# ESP-USB.net
KiCad netlist of a schematic drawn in Altium Designer
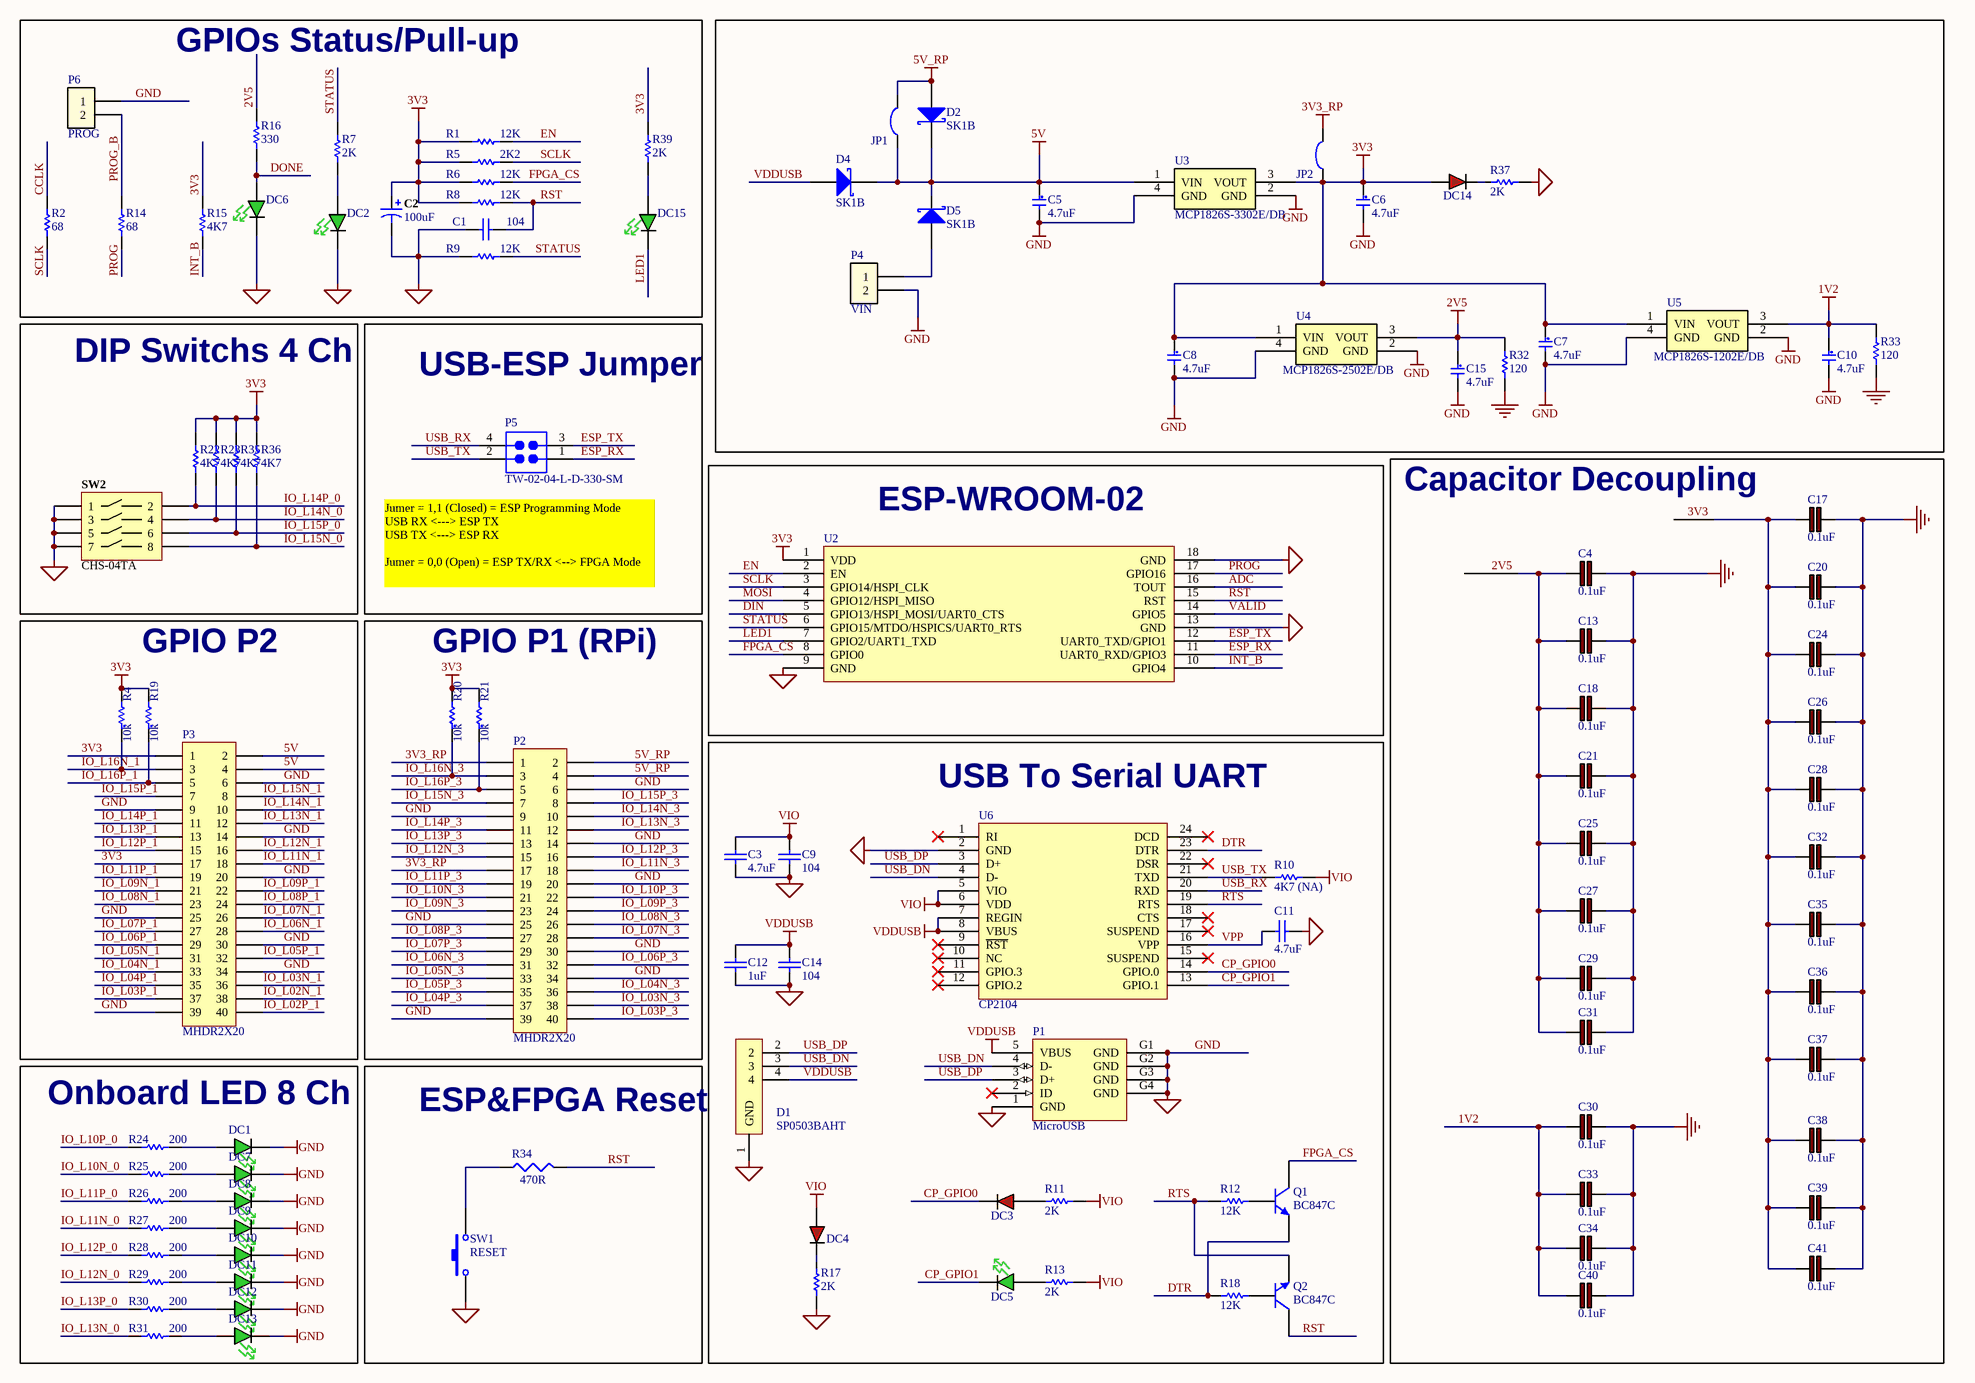
[diagram p0: ESP-USB.SchDoc]

(export (version "E")
  (design (tool "Eeschema 10.0.6"))
  (components
    (comp (ref "C1")
      (value "104")
      (footprint "C0603 - Marked")
      (description "Capacitor 0603")
      (fields (field (name "MFG") "KEMET"))
      (libsource (lib "Miscellaneous Devices") (part "Cap Semi"))
    )
    (comp (ref "C2")
      (value "100 uF Tantalum,")
      (footprint "AVX-CAPC3528_V")
      (description "Capacitor, Tantalum, 100uF 10% 20V MCCT-B (3528)")
      (fields
        (field (name "PARTNUMBER") "TAJB106K020R")
        (field (name "CAPACITANCE") "100uF")
        (field (name "MANUFACTURER") "AVX")
      )
      (libsource (lib "Altium Content Vault") (part "CMP-0279-00001-1"))
    )
    (comp (ref "C3")
      (value "4.7uF")
      (footprint "C0603 - Marked")
      (description "Capacitor 0603")
      (fields (field (name "MFG") "KEMET"))
      (libsource (lib "Miscellaneous Devices") (part "Cap"))
    )
    (comp (ref "C4")
      (value "0.1uF")
      (footprint "C0603 - Marked")
      (description "Capacitor")
      (libsource (lib "MP-LVARM") (part "CAP"))
    )
    (comp (ref "C5")
      (value "4.7uF")
      (footprint "C0603 - Marked")
      (description "4.7uF 6.3volts X5R 10% (MLCC) - SMD/SMT 0603")
      (fields
        (field (name "MANUFACTURER") "Murata Electronics North America")
        (field (name "MANUFACTURER PART NUMBER") "GRM188R60J475KE19D")
      )
      (libsource (lib "mCapacitors") (part "C0603 - GRM188R60J475KE19D"))
    )
    (comp (ref "C6")
      (value "4.7uF")
      (footprint "C0603 - Marked")
      (description "4.7uF 6.3volts X5R 10% (MLCC) - SMD/SMT 0603")
      (fields
        (field (name "MANUFACTURER") "Murata Electronics North America")
        (field (name "MANUFACTURER PART NUMBER") "GRM188R60J475KE19D")
      )
      (libsource (lib "mCapacitors") (part "C0603 - GRM188R60J475KE19D"))
    )
    (comp (ref "C7")
      (value "4.7uF")
      (footprint "C0603 - Marked")
      (description "4.7uF 6.3volts X5R 10% (MLCC) - SMD/SMT 0603")
      (fields
        (field (name "MANUFACTURER") "Murata Electronics North America")
        (field (name "MANUFACTURER PART NUMBER") "GRM188R60J475KE19D")
      )
      (libsource (lib "mCapacitors") (part "C0603 - GRM188R60J475KE19D"))
    )
    (comp (ref "C8")
      (value "4.7uF")
      (footprint "C0603 - Marked")
      (description "4.7uF 6.3volts X5R 10% (MLCC) - SMD/SMT 0603")
      (fields
        (field (name "MANUFACTURER") "Murata Electronics North America")
        (field (name "MANUFACTURER PART NUMBER") "GRM188R60J475KE19D")
      )
      (libsource (lib "mCapacitors") (part "C0603 - GRM188R60J475KE19D"))
    )
    (comp (ref "C9")
      (value "104")
      (footprint "C0603 - Marked")
      (description "Capacitor 0603")
      (fields (field (name "MFG") "KEMET"))
      (libsource (lib "Miscellaneous Devices") (part "Cap Semi"))
    )
    (comp (ref "C10")
      (value "4.7uF")
      (footprint "C0603 - Marked")
      (description "4.7uF 6.3volts X5R 10% (MLCC) - SMD/SMT 0603")
      (fields
        (field (name "MANUFACTURER") "Murata Electronics North America")
        (field (name "MANUFACTURER PART NUMBER") "GRM188R60J475KE19D")
      )
      (libsource (lib "mCapacitors") (part "C0603 - GRM188R60J475KE19D"))
    )
    (comp (ref "C11")
      (value "4.7uF")
      (footprint "C0603 - Marked")
      (description "Capacitor 0603")
      (fields (field (name "MFG") "KEMET"))
      (libsource (lib "Miscellaneous Devices") (part "Cap"))
    )
    (comp (ref "C12")
      (value "1uF")
      (footprint "C0603 - Marked")
      (description "Capacitor 0603")
      (fields (field (name "MFG") "KEMET"))
      (libsource (lib "Miscellaneous Devices") (part "Cap Semi"))
    )
    (comp (ref "C13")
      (value "0.1uF")
      (footprint "C0603 - Marked")
      (description "Capacitor")
      (libsource (lib "MP-LVARM") (part "CAP"))
    )
    (comp (ref "C14")
      (value "104")
      (footprint "C0603 - Marked")
      (description "Capacitor 0603")
      (fields (field (name "MFG") "KEMET"))
      (libsource (lib "Miscellaneous Devices") (part "Cap Semi"))
    )
    (comp (ref "C15")
      (value "4.7uF")
      (footprint "C0603 - Marked")
      (description "4.7uF 6.3volts X5R 10% (MLCC) - SMD/SMT 0603")
      (fields
        (field (name "MANUFACTURER") "Murata Electronics North America")
        (field (name "MANUFACTURER PART NUMBER") "GRM188R60J475KE19D")
      )
      (libsource (lib "mCapacitors") (part "C0603 - GRM188R60J475KE19D"))
    )
    (comp (ref "C17")
      (value "0.1uF")
      (footprint "C0603 - Marked")
      (description "Capacitor")
      (libsource (lib "MP-LVARM") (part "CAP"))
    )
    (comp (ref "C18")
      (value "0.1uF")
      (footprint "C0603 - Marked")
      (description "Capacitor")
      (libsource (lib "MP-LVARM") (part "CAP"))
    )
    (comp (ref "C20")
      (value "0.1uF")
      (footprint "C0603 - Marked")
      (description "Capacitor")
      (libsource (lib "MP-LVARM") (part "CAP"))
    )
    (comp (ref "C21")
      (value "0.1uF")
      (footprint "C0603 - Marked")
      (description "Capacitor")
      (libsource (lib "MP-LVARM") (part "CAP"))
    )
    (comp (ref "C24")
      (value "0.1uF")
      (footprint "C0603 - Marked")
      (description "Capacitor")
      (libsource (lib "MP-LVARM") (part "CAP"))
    )
    (comp (ref "C25")
      (value "0.1uF")
      (footprint "C0603 - Marked")
      (description "Capacitor")
      (libsource (lib "MP-LVARM") (part "CAP"))
    )
    (comp (ref "C26")
      (value "0.1uF")
      (footprint "C0603 - Marked")
      (description "Capacitor")
      (libsource (lib "MP-LVARM") (part "CAP"))
    )
    (comp (ref "C27")
      (value "0.1uF")
      (footprint "C0603 - Marked")
      (description "Capacitor")
      (libsource (lib "MP-LVARM") (part "CAP"))
    )
    (comp (ref "C28")
      (value "0.1uF")
      (footprint "C0603 - Marked")
      (description "Capacitor")
      (libsource (lib "MP-LVARM") (part "CAP"))
    )
    (comp (ref "C29")
      (value "0.1uF")
      (footprint "C0603 - Marked")
      (description "Capacitor")
      (libsource (lib "MP-LVARM") (part "CAP"))
    )
    (comp (ref "C30")
      (value "0.1uF")
      (footprint "C0603 - Marked")
      (description "Capacitor")
      (libsource (lib "MicroLVARM") (part "CAP"))
    )
    (comp (ref "C31")
      (value "0.1uF")
      (footprint "C0603 - Marked")
      (description "Capacitor")
      (libsource (lib "MP-LVARM") (part "CAP"))
    )
    (comp (ref "C32")
      (value "0.1uF")
      (footprint "C0603 - Marked")
      (description "Capacitor")
      (libsource (lib "MP-LVARM") (part "CAP"))
    )
    (comp (ref "C33")
      (value "0.1uF")
      (footprint "C0603 - Marked")
      (description "Capacitor")
      (libsource (lib "MP-LVARM") (part "CAP"))
    )
    (comp (ref "C34")
      (value "0.1uF")
      (footprint "C0603 - Marked")
      (description "Capacitor")
      (libsource (lib "MP-LVARM") (part "CAP"))
    )
    (comp (ref "C35")
      (value "0.1uF")
      (footprint "C0603 - Marked")
      (description "Capacitor")
      (libsource (lib "MP-LVARM") (part "CAP"))
    )
    (comp (ref "C36")
      (value "0.1uF")
      (footprint "C0603 - Marked")
      (description "Capacitor")
      (libsource (lib "MP-LVARM") (part "CAP"))
    )
    (comp (ref "C37")
      (value "0.1uF")
      (footprint "C0603 - Marked")
      (description "Capacitor")
      (libsource (lib "MP-LVARM") (part "CAP"))
    )
    (comp (ref "C38")
      (value "0.1uF")
      (footprint "C0603 - Marked")
      (description "Capacitor")
      (libsource (lib "MP-LVARM") (part "CAP"))
    )
    (comp (ref "C39")
      (value "0.1uF")
      (footprint "C0603 - Marked")
      (description "Capacitor")
      (libsource (lib "MP-LVARM") (part "CAP"))
    )
    (comp (ref "C40")
      (value "0.1uF")
      (footprint "C0603 - Marked")
      (description "Capacitor")
      (libsource (lib "MP-LVARM") (part "CAP"))
    )
    (comp (ref "C41")
      (value "0.1uF")
      (footprint "C0603 - Marked")
      (description "Capacitor")
      (libsource (lib "MP-LVARM") (part "CAP"))
    )
    (comp (ref "D1")
      (value "SP0503BAHT")
      (footprint "SOT143-4")
      (description "TVS DIODE 5.5VWM 8.5VC SOT143")
      (fields (field (name "MFG") "GTK"))
      (libsource (lib "nEWLibrary") (part "SP0503BAHT"))
    )
    (comp (ref "D2")
      (value "SK1B")
      (footprint "EDIS_SMA")
      (description "Schottky Diode")
      (fields (field (name "MFG") "EIC"))
      (libsource (lib "QWAVE-WiFi-101") (part "D Schottky"))
    )
    (comp (ref "D4")
      (value "SK1B")
      (footprint "EDIS_SMA")
      (description "Schottky Diode")
      (fields (field (name "MFG") "EIC"))
      (libsource (lib "QWAVE-WiFi-101") (part "D Schottky"))
    )
    (comp (ref "D5")
      (value "SK1B")
      (footprint "EDIS_SMA")
      (description "Schottky Diode")
      (fields (field (name "MFG") "EIC"))
      (libsource (lib "QWAVE-WiFi-101") (part "D Schottky"))
    )
    (comp (ref "DC1")
      (value "~")
      (footprint "LED_0603 - GREEN")
      (description "LED 1.6X0.8MM 570NM GRN CLR SMD")
      (fields
        (field (name "MANUFACTURER") "Kingbright Corp")
        (field (name "MANUFACTURER PART NUMBER") "APT1608CGCK")
      )
      (libsource (lib "mDiode") (part "APT1608CGCK"))
    )
    (comp (ref "DC2")
      (value "~")
      (footprint "LED_0603 - GREEN")
      (description "LED 1.6X0.8MM 570NM GRN CLR SMD")
      (fields
        (field (name "MANUFACTURER") "Kingbright Corp")
        (field (name "MANUFACTURER PART NUMBER") "APT1608CGCK")
      )
      (libsource (lib "mDiode") (part "APT1608CGCK"))
    )
    (comp (ref "DC3")
      (value "598-8010-107F")
      (footprint "LED_0603 - RED")
      (description "LED ALINGAP RED CLEAR 0603 SMD")
      (fields (field (name "MANUFACTURER") "Dialight"))
      (libsource (lib "mDiode") (part "LED0603 - 598-8010-107F"))
    )
    (comp (ref "DC4")
      (value "598-8010-107F")
      (footprint "LED_0603 - RED")
      (description "LED ALINGAP RED CLEAR 0603 SMD")
      (fields (field (name "MANUFACTURER") "Dialight"))
      (libsource (lib "mDiode") (part "LED0603 - 598-8010-107F"))
    )
    (comp (ref "DC5")
      (value "~")
      (footprint "LED_0603 - GREEN")
      (description "LED 1.6X0.8MM 570NM GRN CLR SMD")
      (fields
        (field (name "MANUFACTURER") "Kingbright Corp")
        (field (name "MANUFACTURER PART NUMBER") "APT1608CGCK")
      )
      (libsource (lib "mDiode") (part "APT1608CGCK"))
    )
    (comp (ref "DC6")
      (value "~")
      (footprint "LED_0603 - GREEN")
      (description "LED 1.6X0.8MM 570NM GRN CLR SMD")
      (fields
        (field (name "MANUFACTURER") "Kingbright Corp")
        (field (name "MANUFACTURER PART NUMBER") "APT1608CGCK")
      )
      (libsource (lib "mDiode") (part "APT1608CGCK"))
    )
    (comp (ref "DC7")
      (value "~")
      (footprint "LED_0603 - GREEN")
      (description "LED 1.6X0.8MM 570NM GRN CLR SMD")
      (fields
        (field (name "MANUFACTURER") "Kingbright Corp")
        (field (name "MANUFACTURER PART NUMBER") "APT1608CGCK")
      )
      (libsource (lib "mDiode") (part "APT1608CGCK"))
    )
    (comp (ref "DC8")
      (value "~")
      (footprint "LED_0603 - GREEN")
      (description "LED 1.6X0.8MM 570NM GRN CLR SMD")
      (fields
        (field (name "MANUFACTURER") "Kingbright Corp")
        (field (name "MANUFACTURER PART NUMBER") "APT1608CGCK")
      )
      (libsource (lib "mDiode") (part "APT1608CGCK"))
    )
    (comp (ref "DC9")
      (value "~")
      (footprint "LED_0603 - GREEN")
      (description "LED 1.6X0.8MM 570NM GRN CLR SMD")
      (fields
        (field (name "MANUFACTURER") "Kingbright Corp")
        (field (name "MANUFACTURER PART NUMBER") "APT1608CGCK")
      )
      (libsource (lib "mDiode") (part "APT1608CGCK"))
    )
    (comp (ref "DC10")
      (value "~")
      (footprint "LED_0603 - GREEN")
      (description "LED 1.6X0.8MM 570NM GRN CLR SMD")
      (fields
        (field (name "MANUFACTURER") "Kingbright Corp")
        (field (name "MANUFACTURER PART NUMBER") "APT1608CGCK")
      )
      (libsource (lib "mDiode") (part "APT1608CGCK"))
    )
    (comp (ref "DC11")
      (value "~")
      (footprint "LED_0603 - GREEN")
      (description "LED 1.6X0.8MM 570NM GRN CLR SMD")
      (fields
        (field (name "MANUFACTURER") "Kingbright Corp")
        (field (name "MANUFACTURER PART NUMBER") "APT1608CGCK")
      )
      (libsource (lib "mDiode") (part "APT1608CGCK"))
    )
    (comp (ref "DC12")
      (value "~")
      (footprint "LED_0603 - GREEN")
      (description "LED 1.6X0.8MM 570NM GRN CLR SMD")
      (fields
        (field (name "MANUFACTURER") "Kingbright Corp")
        (field (name "MANUFACTURER PART NUMBER") "APT1608CGCK")
      )
      (libsource (lib "mDiode") (part "APT1608CGCK"))
    )
    (comp (ref "DC13")
      (value "~")
      (footprint "LED_0603 - GREEN")
      (description "LED 1.6X0.8MM 570NM GRN CLR SMD")
      (fields
        (field (name "MANUFACTURER") "Kingbright Corp")
        (field (name "MANUFACTURER PART NUMBER") "APT1608CGCK")
      )
      (libsource (lib "mDiode") (part "APT1608CGCK"))
    )
    (comp (ref "DC14")
      (value "598-8010-107F")
      (footprint "LED_0603 - RED")
      (description "LED ALINGAP RED CLEAR 0603 SMD")
      (fields (field (name "MANUFACTURER") "Dialight"))
      (libsource (lib "mDiode") (part "LED0603 - 598-8010-107F"))
    )
    (comp (ref "DC15")
      (value "~")
      (footprint "LED_0603 - GREEN")
      (description "LED 1.6X0.8MM 570NM GRN CLR SMD")
      (fields
        (field (name "MANUFACTURER") "Kingbright Corp")
        (field (name "MANUFACTURER PART NUMBER") "APT1608CGCK")
      )
      (libsource (lib "mDiode") (part "APT1608CGCK"))
    )
    (comp (ref "JP1")
      (value "Solder Jumper")
      (footprint "SOLDER_JUMPER")
      (description "Solder/Configuration Jumper")
      (fields (field (name "MANUFACTURER") "n/a"))
      (libsource (lib "mConnector") (part "Solder Jumper"))
    )
    (comp (ref "JP2")
      (value "Solder Jumper")
      (footprint "SOLDER_JUMPER")
      (description "Solder/Configuration Jumper")
      (fields (field (name "MANUFACTURER") "n/a"))
      (libsource (lib "mConnector") (part "Solder Jumper"))
    )
    (comp (ref "P1")
      (value "MicroUSB")
      (footprint "MICRO-USB-CON")
      (description "Micro USB 5Pins,Female B type Right Angle, SMT")
      (fields (field (name "MFG") "GTK"))
      (libsource (lib "ThaiEasySymbol") (part "ESOC004"))
    )
    (comp (ref "P2")
      (value "MHDR2X20")
      (footprint "Raspberry Con")
      (description "Header, 20-Pin, Dual row")
      (fields (field (name "PUBLISHER") "Altium Limited"))
      (libsource (lib "Miscellaneous Connectors") (part "MHDR2X20"))
    )
    (comp (ref "P3")
      (value "MHDR2X20")
      (footprint "Raspberry Con")
      (description "Header, 20-Pin, Dual row")
      (fields (field (name "PUBLISHER") "Altium Limited"))
      (libsource (lib "Miscellaneous Connectors") (part "MHDR2X20"))
    )
    (comp (ref "P4")
      (value "VIN")
      (footprint "HEADER_2_40_100 THRU SIP")
      (description "Header 2 pin")
      (libsource (lib "mConnector") (part "Header2"))
    )
    (comp (ref "P5")
      (value "TW-02-04-L-D-330-SM")
      (footprint "SMTC-TW-02-04-X-D-330-SM")
      (description "SMT Board Stacker, Vertical, -55 to 125 degC, 2 mm Pitch, 4-Pin, Male, RoHS")
      (fields (field (name "MANUFACTURER") "Samtec"))
      (libsource (lib "Altium Content Vault") (part "CMP-1029-00319-1"))
    )
    (comp (ref "P6")
      (value "PROG")
      (footprint "HEADER_2_40_100 THRU SIP")
      (description "Header 2 pin")
      (libsource (lib "mConnector") (part "Header2"))
    )
    (comp (ref "Q1")
      (value "BC847C")
      (footprint "SOT-23")
      (description "NPN Bipolar Transistor")
      (fields (field (name "MFG") "PHILIPS/NXP"))
      (libsource (lib "Miscellaneous Devices") (part "NPN"))
    )
    (comp (ref "Q2")
      (value "BC847C")
      (footprint "SOT-23")
      (description "NPN Bipolar Transistor")
      (fields (field (name "MFG") "PHILIPS/NXP"))
      (libsource (lib "Miscellaneous Devices") (part "NPN"))
    )
    (comp (ref "R1")
      (value "12K")
      (footprint "R0603")
      (description "Resistor 0603")
      (fields (field (name "MFG") "ROHM"))
      (libsource (lib "Miscellaneous Devices") (part "Res Semi"))
    )
    (comp (ref "R2")
      (value "68")
      (footprint "R0603")
      (description "Resistor 0603")
      (fields (field (name "MFG") "ROHM"))
      (libsource (lib "Miscellaneous Devices") (part "Res Semi"))
    )
    (comp (ref "R4")
      (value "10k")
      (footprint "R0603")
      (description "10k Thick Film Resistors - SMD 1/10watt 10Kohms 1%")
      (fields
        (field (name "MANUFACTURER") "Vishay Dale")
        (field (name "MANUFACTURER PART NUMBER") "CRCW060310K0FKEA")
      )
      (libsource (lib "mResistors") (part "R0603 - CRCW060310K0FKEA"))
    )
    (comp (ref "R5")
      (value "2K2")
      (footprint "R0603")
      (description "Resistor 0603")
      (fields (field (name "MFG") "ROHM"))
      (libsource (lib "Miscellaneous Devices") (part "Res Semi"))
    )
    (comp (ref "R6")
      (value "12K")
      (footprint "R0603")
      (description "Resistor 0603")
      (fields (field (name "MFG") "ROHM"))
      (libsource (lib "Miscellaneous Devices") (part "Res Semi"))
    )
    (comp (ref "R7")
      (value "2K")
      (footprint "R0603")
      (description "Resistor 0603")
      (fields (field (name "MFG") "ROHM"))
      (libsource (lib "Miscellaneous Devices") (part "Res Semi"))
    )
    (comp (ref "R8")
      (value "12K")
      (footprint "R0603")
      (description "Resistor 0603")
      (fields (field (name "MFG") "ROHM"))
      (libsource (lib "Miscellaneous Devices") (part "Res Semi"))
    )
    (comp (ref "R9")
      (value "12K")
      (footprint "R0603")
      (description "Resistor 0603")
      (fields (field (name "MFG") "ROHM"))
      (libsource (lib "Miscellaneous Devices") (part "Res Semi"))
    )
    (comp (ref "R10")
      (value "4K7 (NA)")
      (footprint "R0603")
      (description "Resistor 0603")
      (libsource (lib "Miscellaneous Devices") (part "Res Semi"))
    )
    (comp (ref "R11")
      (value "2K")
      (footprint "R0603")
      (description "Resistor 0603")
      (fields (field (name "MFG") "ROHM"))
      (libsource (lib "Miscellaneous Devices") (part "Res Semi"))
    )
    (comp (ref "R12")
      (value "12K")
      (footprint "R0603")
      (description "Resistor 0603")
      (fields (field (name "MFG") "ROHM"))
      (libsource (lib "Miscellaneous Devices") (part "Res Semi"))
    )
    (comp (ref "R13")
      (value "2K")
      (footprint "R0603")
      (description "Resistor 0603")
      (fields (field (name "MFG") "ROHM"))
      (libsource (lib "Miscellaneous Devices") (part "Res Semi"))
    )
    (comp (ref "R14")
      (value "68")
      (footprint "R0603")
      (description "Resistor 0603")
      (fields (field (name "MFG") "ROHM"))
      (libsource (lib "Miscellaneous Devices") (part "Res Semi"))
    )
    (comp (ref "R15")
      (value "4K7")
      (footprint "R0603")
      (description "Resistor 0603")
      (fields (field (name "MFG") "ROHM"))
      (libsource (lib "Miscellaneous Devices") (part "Res Semi"))
    )
    (comp (ref "R16")
      (value "330")
      (footprint "R0603")
      (description "Resistor 0603")
      (fields (field (name "MFG") "ROHM"))
      (libsource (lib "Miscellaneous Devices") (part "Res Semi"))
    )
    (comp (ref "R17")
      (value "2K")
      (footprint "R0603")
      (description "Resistor 0603")
      (fields (field (name "MFG") "ROHM"))
      (libsource (lib "Miscellaneous Devices") (part "Res Semi"))
    )
    (comp (ref "R18")
      (value "12K")
      (footprint "R0603")
      (description "Resistor 0603")
      (fields (field (name "MFG") "ROHM"))
      (libsource (lib "Miscellaneous Devices") (part "Res Semi"))
    )
    (comp (ref "R19")
      (value "10k")
      (footprint "R0603")
      (description "10k Thick Film Resistors - SMD 1/10watt 10Kohms 1%")
      (fields
        (field (name "MANUFACTURER") "Vishay Dale")
        (field (name "MANUFACTURER PART NUMBER") "CRCW060310K0FKEA")
      )
      (libsource (lib "mResistors") (part "R0603 - CRCW060310K0FKEA"))
    )
    (comp (ref "R20")
      (value "10k")
      (footprint "R0603")
      (description "10k Thick Film Resistors - SMD 1/10watt 10Kohms 1%")
      (fields
        (field (name "MANUFACTURER") "Vishay Dale")
        (field (name "MANUFACTURER PART NUMBER") "CRCW060310K0FKEA")
      )
      (libsource (lib "mResistors") (part "R0603 - CRCW060310K0FKEA"))
    )
    (comp (ref "R21")
      (value "10k")
      (footprint "R0603")
      (description "10k Thick Film Resistors - SMD 1/10watt 10Kohms 1%")
      (fields
        (field (name "MANUFACTURER") "Vishay Dale")
        (field (name "MANUFACTURER PART NUMBER") "CRCW060310K0FKEA")
      )
      (libsource (lib "mResistors") (part "R0603 - CRCW060310K0FKEA"))
    )
    (comp (ref "R22")
      (value "4K7")
      (footprint "R0603")
      (description "Resistor 0603")
      (fields (field (name "MFG") "ROHM"))
      (libsource (lib "Miscellaneous Devices") (part "Res Semi"))
    )
    (comp (ref "R23")
      (value "4K7")
      (footprint "R0603")
      (description "Resistor 0603")
      (fields (field (name "MFG") "ROHM"))
      (libsource (lib "Miscellaneous Devices") (part "Res Semi"))
    )
    (comp (ref "R24")
      (value "200")
      (footprint "R0603")
      (description "RES 200 OHM 1/10W 1% 0603 SMD")
      (fields
        (field (name "MANUFACTURER") "Panasonic - ECG")
        (field (name "MANUFACTURER PART NUMBER") "ERJ-3EKF2000V")
      )
      (libsource (lib "eResistors") (part "ERJ-3EKF2000V"))
    )
    (comp (ref "R25")
      (value "200")
      (footprint "R0603")
      (description "RES 200 OHM 1/10W 1% 0603 SMD")
      (fields
        (field (name "MANUFACTURER") "Panasonic - ECG")
        (field (name "MANUFACTURER PART NUMBER") "ERJ-3EKF2000V")
      )
      (libsource (lib "eResistors") (part "ERJ-3EKF2000V"))
    )
    (comp (ref "R26")
      (value "200")
      (footprint "R0603")
      (description "RES 200 OHM 1/10W 1% 0603 SMD")
      (fields
        (field (name "MANUFACTURER") "Panasonic - ECG")
        (field (name "MANUFACTURER PART NUMBER") "ERJ-3EKF2000V")
      )
      (libsource (lib "eResistors") (part "ERJ-3EKF2000V"))
    )
    (comp (ref "R27")
      (value "200")
      (footprint "R0603")
      (description "RES 200 OHM 1/10W 1% 0603 SMD")
      (fields
        (field (name "MANUFACTURER") "Panasonic - ECG")
        (field (name "MANUFACTURER PART NUMBER") "ERJ-3EKF2000V")
      )
      (libsource (lib "eResistors") (part "ERJ-3EKF2000V"))
    )
    (comp (ref "R28")
      (value "200")
      (footprint "R0603")
      (description "RES 200 OHM 1/10W 1% 0603 SMD")
      (fields
        (field (name "MANUFACTURER") "Panasonic - ECG")
        (field (name "MANUFACTURER PART NUMBER") "ERJ-3EKF2000V")
      )
      (libsource (lib "eResistors") (part "ERJ-3EKF2000V"))
    )
    (comp (ref "R29")
      (value "200")
      (footprint "R0603")
      (description "RES 200 OHM 1/10W 1% 0603 SMD")
      (fields
        (field (name "MANUFACTURER") "Panasonic - ECG")
        (field (name "MANUFACTURER PART NUMBER") "ERJ-3EKF2000V")
      )
      (libsource (lib "eResistors") (part "ERJ-3EKF2000V"))
    )
    (comp (ref "R30")
      (value "200")
      (footprint "R0603")
      (description "RES 200 OHM 1/10W 1% 0603 SMD")
      (fields
        (field (name "MANUFACTURER") "Panasonic - ECG")
        (field (name "MANUFACTURER PART NUMBER") "ERJ-3EKF2000V")
      )
      (libsource (lib "eResistors") (part "ERJ-3EKF2000V"))
    )
    (comp (ref "R31")
      (value "200")
      (footprint "R0603")
      (description "RES 200 OHM 1/10W 1% 0603 SMD")
      (fields
        (field (name "MANUFACTURER") "Panasonic - ECG")
        (field (name "MANUFACTURER PART NUMBER") "ERJ-3EKF2000V")
      )
      (libsource (lib "eResistors") (part "ERJ-3EKF2000V"))
    )
    (comp (ref "R32")
      (value "120")
      (footprint "R0603")
      (description "Resistor 0603")
      (fields (field (name "MFG") "ROHM"))
      (libsource (lib "Miscellaneous Devices") (part "Res Semi"))
    )
    (comp (ref "R33")
      (value "120")
      (footprint "R0603")
      (description "Resistor 0603")
      (fields (field (name "MFG") "ROHM"))
      (libsource (lib "Miscellaneous Devices") (part "Res Semi"))
    )
    (comp (ref "R34")
      (value "470R")
      (footprint "J1-0603")
      (description "Resistor")
      (fields (field (name "Comment") "470") (field (name "PUBLISHER") "Altium Limited"))
      (libsource (lib "Miscellaneous Devices") (part "Res3"))
    )
    (comp (ref "R35")
      (value "4K7")
      (footprint "R0603")
      (description "Resistor 0603")
      (fields (field (name "MFG") "ROHM"))
      (libsource (lib "Miscellaneous Devices") (part "Res Semi"))
    )
    (comp (ref "R36")
      (value "4K7")
      (footprint "R0603")
      (description "Resistor 0603")
      (fields (field (name "MFG") "ROHM"))
      (libsource (lib "Miscellaneous Devices") (part "Res Semi"))
    )
    (comp (ref "R37")
      (value "2K")
      (footprint "R0603")
      (description "Resistor 0603")
      (fields (field (name "MFG") "ROHM"))
      (libsource (lib "Miscellaneous Devices") (part "Res Semi"))
    )
    (comp (ref "R39")
      (value "2K")
      (footprint "R0603")
      (description "Resistor 0603")
      (fields (field (name "MFG") "ROHM"))
      (libsource (lib "Miscellaneous Devices") (part "Res Semi"))
    )
    (comp (ref "SW1")
      (value "RESET")
      (footprint "SW_MINI")
      (description "Tact Switch")
      (fields (field (name "MFG") "ALPS"))
      (libsource (lib "QWAVE-WiFi-101") (part "SW-PB"))
    )
    (comp (ref "SW2")
      (value "CHS-04TA")
      (footprint "EHS104L")
      (description "SWITCH DIP 4-POS SLIDE SMD 6V")
      (fields (field (name "MANUFACTURER") "Copal Electronics Inc"))
      (libsource (lib "Arduino - FPGA Development Board") (part "CHS-04TA"))
    )
    (comp (ref "U2")
      (value "ESP8266_WROOM_02")
      (footprint "ESP WROOM02-Fit Size")
      (description "WiFi Serial Transceiver Module (ESP8266)")
      (fields (field (name "MFG") "ESPRESSIF"))
      (libsource (lib "nEWLibrary") (part "ESP8266 WROOM 02"))
    )
    (comp (ref "U3")
      (value "MCP1826S-3302E/DB")
      (footprint "SOT223")
      (description "LDO REG 1A 3.3V SOT223-3")
      (fields (field (name "MANUFACTURER") "Microchip Technology"))
      (libsource (lib "mIC") (part "REG - MCP1826S-3302E/DB"))
    )
    (comp (ref "U4")
      (value "MCP1826S-2502E/DB")
      (footprint "SOT223")
      (description "IC LDO REG 1A 2.5V SOT223-3")
      (fields
        (field (name "MANUFACTURER") "Microchip Technology")
        (field (name "MANUFACTURER PART NUMBER") "MCP1826S-1202E/DB")
      )
      (libsource (lib "eIC") (part "MCP1826S-1202E/DB"))
    )
    (comp (ref "U5")
      (value "MCP1826S-1202E/DB")
      (footprint "SOT223")
      (description "IC LDO REG 1A 1.2V SOT223-3")
      (fields (field (name "MANUFACTURER") "Microchip Technology"))
      (libsource (lib "eIC") (part "MCP1826S-1202E/DB"))
    )
    (comp (ref "U6")
      (value "CP2104")
      (footprint "QFN24 - duplicate")
      (description "IC SGL USB-TO-UART BRIDGE 24QFN")
      (fields (field (name "MFG") "Silicon Labs"))
      (libsource (lib "nEWLibrary") (part "CP2104"))
    )
  )
  (nets
    (net (code "1") (name "/ADC") (class "Default")
      (node (ref "U2") (pin "16") (pinfunction "TOUT_16") (pintype "passive"))
    )
    (net (code "2") (name "/CCLK") (class "Default")
      (node (ref "R2") (pin "1") (pinfunction "1_1") (pintype "passive"))
    )
    (net (code "3") (name "/CP_GPIO0") (class "Default")
      (node (ref "DC3") (pin "C") (pinfunction "C_C") (pintype "passive"))
      (node (ref "U6") (pin "14") (pinfunction "GPIO.0_14") (pintype "passive"))
    )
    (net (code "4") (name "/CP_GPIO1") (class "Default")
      (node (ref "DC5") (pin "C") (pinfunction "C_C") (pintype "passive"))
      (node (ref "U6") (pin "13") (pinfunction "GPIO.1_13") (pintype "passive"))
    )
    (net (code "5") (name "/DIN") (class "Default")
      (node (ref "U2") (pin "5") (pinfunction "GPIO13/HSPI_MOSI/UART0_CTS_5") (pintype "passive"))
    )
    (net (code "6") (name "/DONE") (class "Default")
      (node (ref "DC6") (pin "A") (pinfunction "A_A") (pintype "passive"))
      (node (ref "R16") (pin "2") (pinfunction "2_2") (pintype "passive"))
    )
    (net (code "7") (name "/DTR") (class "Default")
      (node (ref "Q1") (pin "2") (pinfunction "E_2") (pintype "passive"))
      (node (ref "R18") (pin "2") (pinfunction "2_2") (pintype "passive"))
      (node (ref "U6") (pin "23") (pinfunction "DTR_23") (pintype "passive"))
    )
    (net (code "8") (name "/EN") (class "Default")
      (node (ref "R1") (pin "1") (pinfunction "1_1") (pintype "passive"))
      (node (ref "U2") (pin "2") (pinfunction "EN_2") (pintype "passive"))
    )
    (net (code "9") (name "/ESP_RX") (class "Default")
      (node (ref "P5") (pin "1") (pinfunction "1_1") (pintype "passive"))
      (node (ref "U2") (pin "11") (pinfunction "UART0_RXD/GPIO3_11") (pintype "passive"))
    )
    (net (code "10") (name "/ESP_TX") (class "Default")
      (node (ref "P5") (pin "3") (pinfunction "3_3") (pintype "passive"))
      (node (ref "U2") (pin "12") (pinfunction "UART0_TXD/GPIO1_12") (pintype "passive"))
    )
    (net (code "11") (name "/FPGA_CS") (class "Default")
      (node (ref "Q1") (pin "3") (pinfunction "C_3") (pintype "passive"))
      (node (ref "R6") (pin "1") (pinfunction "1_1") (pintype "passive"))
      (node (ref "U2") (pin "8") (pinfunction "GPIO0_8") (pintype "passive"))
    )
    (net (code "12") (name "/INT_B") (class "Default")
      (node (ref "R15") (pin "2") (pinfunction "2_2") (pintype "passive"))
      (node (ref "U2") (pin "10") (pinfunction "GPIO4_10") (pintype "passive"))
    )
    (net (code "13") (name "/IO_L02N_1") (class "Default")
      (node (ref "P3") (pin "38") (pinfunction "38_38") (pintype "passive"))
    )
    (net (code "14") (name "/IO_L02P_1") (class "Default")
      (node (ref "P3") (pin "40") (pinfunction "40_40") (pintype "passive"))
    )
    (net (code "15") (name "/IO_L03N_1") (class "Default")
      (node (ref "P3") (pin "36") (pinfunction "36_36") (pintype "passive"))
    )
    (net (code "16") (name "/IO_L03N_3") (class "Default")
      (node (ref "P2") (pin "38") (pinfunction "38_38") (pintype "passive"))
    )
    (net (code "17") (name "/IO_L03P_1") (class "Default")
      (node (ref "P3") (pin "37") (pinfunction "37_37") (pintype "passive"))
    )
    (net (code "18") (name "/IO_L03P_3") (class "Default")
      (node (ref "P2") (pin "40") (pinfunction "40_40") (pintype "passive"))
    )
    (net (code "19") (name "/IO_L04N_1") (class "Default")
      (node (ref "P3") (pin "33") (pinfunction "33_33") (pintype "passive"))
    )
    (net (code "20") (name "/IO_L04N_3") (class "Default")
      (node (ref "P2") (pin "36") (pinfunction "36_36") (pintype "passive"))
    )
    (net (code "21") (name "/IO_L04P_1") (class "Default")
      (node (ref "P3") (pin "35") (pinfunction "35_35") (pintype "passive"))
    )
    (net (code "22") (name "/IO_L04P_3") (class "Default")
      (node (ref "P2") (pin "37") (pinfunction "37_37") (pintype "passive"))
    )
    (net (code "23") (name "/IO_L05N_1") (class "Default")
      (node (ref "P3") (pin "31") (pinfunction "31_31") (pintype "passive"))
    )
    (net (code "24") (name "/IO_L05N_3") (class "Default")
      (node (ref "P2") (pin "33") (pinfunction "33_33") (pintype "passive"))
    )
    (net (code "25") (name "/IO_L05P_1") (class "Default")
      (node (ref "P3") (pin "32") (pinfunction "32_32") (pintype "passive"))
    )
    (net (code "26") (name "/IO_L05P_3") (class "Default")
      (node (ref "P2") (pin "35") (pinfunction "35_35") (pintype "passive"))
    )
    (net (code "27") (name "/IO_L06N_1") (class "Default")
      (node (ref "P3") (pin "28") (pinfunction "28_28") (pintype "passive"))
    )
    (net (code "28") (name "/IO_L06N_3") (class "Default")
      (node (ref "P2") (pin "31") (pinfunction "31_31") (pintype "passive"))
    )
    (net (code "29") (name "/IO_L06P_1") (class "Default")
      (node (ref "P3") (pin "29") (pinfunction "29_29") (pintype "passive"))
    )
    (net (code "30") (name "/IO_L06P_3") (class "Default")
      (node (ref "P2") (pin "32") (pinfunction "32_32") (pintype "passive"))
    )
    (net (code "31") (name "/IO_L07N_1") (class "Default")
      (node (ref "P3") (pin "26") (pinfunction "26_26") (pintype "passive"))
    )
    (net (code "32") (name "/IO_L07N_3") (class "Default")
      (node (ref "P2") (pin "28") (pinfunction "28_28") (pintype "passive"))
    )
    (net (code "33") (name "/IO_L07P_1") (class "Default")
      (node (ref "P3") (pin "27") (pinfunction "27_27") (pintype "passive"))
    )
    (net (code "34") (name "/IO_L07P_3") (class "Default")
      (node (ref "P2") (pin "29") (pinfunction "29_29") (pintype "passive"))
    )
    (net (code "35") (name "/IO_L08N_1") (class "Default")
      (node (ref "P3") (pin "23") (pinfunction "23_23") (pintype "passive"))
    )
    (net (code "36") (name "/IO_L08N_3") (class "Default")
      (node (ref "P2") (pin "26") (pinfunction "26_26") (pintype "passive"))
    )
    (net (code "37") (name "/IO_L08P_1") (class "Default")
      (node (ref "P3") (pin "24") (pinfunction "24_24") (pintype "passive"))
    )
    (net (code "38") (name "/IO_L08P_3") (class "Default")
      (node (ref "P2") (pin "27") (pinfunction "27_27") (pintype "passive"))
    )
    (net (code "39") (name "/IO_L09N_1") (class "Default")
      (node (ref "P3") (pin "21") (pinfunction "21_21") (pintype "passive"))
    )
    (net (code "40") (name "/IO_L09N_3") (class "Default")
      (node (ref "P2") (pin "23") (pinfunction "23_23") (pintype "passive"))
    )
    (net (code "41") (name "/IO_L09P_1") (class "Default")
      (node (ref "P3") (pin "22") (pinfunction "22_22") (pintype "passive"))
    )
    (net (code "42") (name "/IO_L09P_3") (class "Default")
      (node (ref "P2") (pin "24") (pinfunction "24_24") (pintype "passive"))
    )
    (net (code "43") (name "/IO_L10N_0") (class "Default")
      (node (ref "R25") (pin "2") (pinfunction "2_2") (pintype "passive"))
    )
    (net (code "44") (name "/IO_L10N_3") (class "Default")
      (node (ref "P2") (pin "21") (pinfunction "21_21") (pintype "passive"))
    )
    (net (code "45") (name "/IO_L10P_0") (class "Default")
      (node (ref "R24") (pin "2") (pinfunction "2_2") (pintype "passive"))
    )
    (net (code "46") (name "/IO_L10P_3") (class "Default")
      (node (ref "P2") (pin "22") (pinfunction "22_22") (pintype "passive"))
    )
    (net (code "47") (name "/IO_L11N_0") (class "Default")
      (node (ref "R27") (pin "2") (pinfunction "2_2") (pintype "passive"))
    )
    (net (code "48") (name "/IO_L11N_1") (class "Default")
      (node (ref "P3") (pin "18") (pinfunction "18_18") (pintype "passive"))
    )
    (net (code "49") (name "/IO_L11N_3") (class "Default")
      (node (ref "P2") (pin "18") (pinfunction "18_18") (pintype "passive"))
    )
    (net (code "50") (name "/IO_L11P_0") (class "Default")
      (node (ref "R26") (pin "2") (pinfunction "2_2") (pintype "passive"))
    )
    (net (code "51") (name "/IO_L11P_1") (class "Default")
      (node (ref "P3") (pin "19") (pinfunction "19_19") (pintype "passive"))
    )
    (net (code "52") (name "/IO_L11P_3") (class "Default")
      (node (ref "P2") (pin "19") (pinfunction "19_19") (pintype "passive"))
    )
    (net (code "53") (name "/IO_L12N_0") (class "Default")
      (node (ref "R29") (pin "2") (pinfunction "2_2") (pintype "passive"))
    )
    (net (code "54") (name "/IO_L12N_1") (class "Default")
      (node (ref "P3") (pin "16") (pinfunction "16_16") (pintype "passive"))
    )
    (net (code "55") (name "/IO_L12N_3") (class "Default")
      (node (ref "P2") (pin "15") (pinfunction "15_15") (pintype "passive"))
    )
    (net (code "56") (name "/IO_L12P_0") (class "Default")
      (node (ref "R28") (pin "2") (pinfunction "2_2") (pintype "passive"))
    )
    (net (code "57") (name "/IO_L12P_1") (class "Default")
      (node (ref "P3") (pin "15") (pinfunction "15_15") (pintype "passive"))
    )
    (net (code "58") (name "/IO_L12P_3") (class "Default")
      (node (ref "P2") (pin "16") (pinfunction "16_16") (pintype "passive"))
    )
    (net (code "59") (name "/IO_L13N_0") (class "Default")
      (node (ref "R31") (pin "2") (pinfunction "2_2") (pintype "passive"))
    )
    (net (code "60") (name "/IO_L13N_1") (class "Default")
      (node (ref "P3") (pin "12") (pinfunction "12_12") (pintype "passive"))
    )
    (net (code "61") (name "/IO_L13N_3") (class "Default")
      (node (ref "P2") (pin "12") (pinfunction "12_12") (pintype "passive"))
    )
    (net (code "62") (name "/IO_L13P_0") (class "Default")
      (node (ref "R30") (pin "2") (pinfunction "2_2") (pintype "passive"))
    )
    (net (code "63") (name "/IO_L13P_1") (class "Default")
      (node (ref "P3") (pin "13") (pinfunction "13_13") (pintype "passive"))
    )
    (net (code "64") (name "/IO_L13P_3") (class "Default")
      (node (ref "P2") (pin "13") (pinfunction "13_13") (pintype "passive"))
    )
    (net (code "65") (name "/IO_L14N_0") (class "Default")
      (node (ref "R23") (pin "2") (pinfunction "2_2") (pintype "passive"))
      (node (ref "SW2") (pin "4") (pinfunction "4_4") (pintype "passive"))
    )
    (net (code "66") (name "/IO_L14N_1") (class "Default")
      (node (ref "P3") (pin "10") (pinfunction "10_10") (pintype "passive"))
    )
    (net (code "67") (name "/IO_L14N_3") (class "Default")
      (node (ref "P2") (pin "10") (pinfunction "10_10") (pintype "passive"))
    )
    (net (code "68") (name "/IO_L14P_0") (class "Default")
      (node (ref "R22") (pin "2") (pinfunction "2_2") (pintype "passive"))
      (node (ref "SW2") (pin "2") (pinfunction "2_2") (pintype "passive"))
    )
    (net (code "69") (name "/IO_L14P_1") (class "Default")
      (node (ref "P3") (pin "11") (pinfunction "11_11") (pintype "passive"))
    )
    (net (code "70") (name "/IO_L14P_3") (class "Default")
      (node (ref "P2") (pin "11") (pinfunction "11_11") (pintype "passive"))
    )
    (net (code "71") (name "/IO_L15N_0") (class "Default")
      (node (ref "R36") (pin "2") (pinfunction "2_2") (pintype "passive"))
      (node (ref "SW2") (pin "8") (pinfunction "8_8") (pintype "passive"))
    )
    (net (code "72") (name "/IO_L15N_1") (class "Default")
      (node (ref "P3") (pin "8") (pinfunction "8_8") (pintype "passive"))
    )
    (net (code "73") (name "/IO_L15N_3") (class "Default")
      (node (ref "P2") (pin "7") (pinfunction "7_7") (pintype "passive"))
    )
    (net (code "74") (name "/IO_L15P_0") (class "Default")
      (node (ref "R35") (pin "2") (pinfunction "2_2") (pintype "passive"))
      (node (ref "SW2") (pin "6") (pinfunction "6_6") (pintype "passive"))
    )
    (net (code "75") (name "/IO_L15P_1") (class "Default")
      (node (ref "P3") (pin "7") (pinfunction "7_7") (pintype "passive"))
    )
    (net (code "76") (name "/IO_L15P_3") (class "Default")
      (node (ref "P2") (pin "8") (pinfunction "8_8") (pintype "passive"))
    )
    (net (code "77") (name "/IO_L16N_1") (class "Default")
      (node (ref "P3") (pin "3") (pinfunction "3_3") (pintype "passive"))
      (node (ref "R4") (pin "1") (pinfunction "1_1") (pintype "passive"))
    )
    (net (code "78") (name "/IO_L16N_3") (class "Default")
      (node (ref "P2") (pin "3") (pinfunction "3_3") (pintype "passive"))
      (node (ref "R20") (pin "1") (pinfunction "1_1") (pintype "passive"))
    )
    (net (code "79") (name "/IO_L16P_1") (class "Default")
      (node (ref "P3") (pin "5") (pinfunction "5_5") (pintype "passive"))
      (node (ref "R19") (pin "1") (pinfunction "1_1") (pintype "passive"))
    )
    (net (code "80") (name "/IO_L16P_3") (class "Default")
      (node (ref "P2") (pin "5") (pinfunction "5_5") (pintype "passive"))
      (node (ref "R21") (pin "1") (pinfunction "1_1") (pintype "passive"))
    )
    (net (code "81") (name "/LED1") (class "Default")
      (node (ref "DC15") (pin "C") (pinfunction "C_C") (pintype "passive"))
      (node (ref "U2") (pin "7") (pinfunction "GPIO2/UART1_TXD_7") (pintype "passive"))
    )
    (net (code "82") (name "/MOSI") (class "Default")
      (node (ref "U2") (pin "4") (pinfunction "GPIO12/HSPI_MISO_4") (pintype "passive"))
    )
    (net (code "83") (name "/PROG") (class "Default")
      (node (ref "R14") (pin "2") (pinfunction "2_2") (pintype "passive"))
      (node (ref "U2") (pin "17") (pinfunction "GPIO16_17") (pintype "passive"))
    )
    (net (code "84") (name "/PROG_B") (class "Default")
      (node (ref "P6") (pin "2") (pinfunction "2_2") (pintype "passive"))
      (node (ref "R14") (pin "1") (pinfunction "1_1") (pintype "passive"))
    )
    (net (code "85") (name "/RST") (class "Default")
      (node (ref "C1") (pin "2") (pinfunction "2_2") (pintype "passive"))
      (node (ref "Q2") (pin "3") (pinfunction "C_3") (pintype "passive"))
      (node (ref "R34") (pin "2") (pinfunction "2_2") (pintype "passive"))
      (node (ref "R8") (pin "1") (pinfunction "1_1") (pintype "passive"))
      (node (ref "U2") (pin "15") (pinfunction "RST_15") (pintype "passive"))
    )
    (net (code "86") (name "/RTS") (class "Default")
      (node (ref "Q2") (pin "2") (pinfunction "E_2") (pintype "passive"))
      (node (ref "R12") (pin "2") (pinfunction "2_2") (pintype "passive"))
      (node (ref "U6") (pin "19") (pinfunction "RTS_19") (pintype "passive"))
    )
    (net (code "87") (name "/SCLK") (class "Default")
      (node (ref "R2") (pin "2") (pinfunction "2_2") (pintype "passive"))
      (node (ref "R5") (pin "1") (pinfunction "1_1") (pintype "passive"))
      (node (ref "U2") (pin "3") (pinfunction "GPIO14/HSPI_CLK_3") (pintype "passive"))
    )
    (net (code "88") (name "/STATUS") (class "Default")
      (node (ref "R7") (pin "1") (pinfunction "1_1") (pintype "passive"))
      (node (ref "R9") (pin "1") (pinfunction "1_1") (pintype "passive"))
      (node (ref "U2") (pin "6") (pinfunction "GPIO15/MTDO/HSPICS/UART0_RTS_6") (pintype "passive"))
    )
    (net (code "89") (name "/USB_DN") (class "Default")
      (node (ref "D1") (pin "3") (pinfunction "3_3") (pintype "passive"))
      (node (ref "P1") (pin "4") (pinfunction "D-_4") (pintype "bidirectional"))
      (node (ref "U6") (pin "4") (pinfunction "D-_4") (pintype "passive"))
    )
    (net (code "90") (name "/USB_DP") (class "Default")
      (node (ref "D1") (pin "2") (pinfunction "2_2") (pintype "passive"))
      (node (ref "P1") (pin "3") (pinfunction "D+_3") (pintype "bidirectional"))
      (node (ref "U6") (pin "3") (pinfunction "D+_3") (pintype "passive"))
    )
    (net (code "91") (name "/USB_RX") (class "Default")
      (node (ref "P5") (pin "4") (pinfunction "4_4") (pintype "passive"))
      (node (ref "U6") (pin "20") (pinfunction "RXD_20") (pintype "passive"))
    )
    (net (code "92") (name "/USB_TX") (class "Default")
      (node (ref "P5") (pin "2") (pinfunction "2_2") (pintype "passive"))
      (node (ref "R10") (pin "1") (pinfunction "1_1") (pintype "passive"))
      (node (ref "U6") (pin "21") (pinfunction "TXD_21") (pintype "passive"))
    )
    (net (code "93") (name "/VALID") (class "Default")
      (node (ref "U2") (pin "14") (pinfunction "GPIO5_14") (pintype "passive"))
    )
    (net (code "94") (name "/VPP") (class "Default")
      (node (ref "C11") (pin "1") (pinfunction "1_1") (pintype "passive"))
      (node (ref "U6") (pin "16") (pinfunction "VPP_16") (pintype "passive"))
    )
    (net (code "95") (name "1V2") (class "Default")
      (node (ref "C10") (pin "1") (pinfunction "1_1") (pintype "passive"))
      (node (ref "C30") (pin "1") (pinfunction "1_1") (pintype "passive"))
      (node (ref "C33") (pin "1") (pinfunction "1_1") (pintype "passive"))
      (node (ref "C34") (pin "1") (pinfunction "1_1") (pintype "passive"))
      (node (ref "C40") (pin "1") (pinfunction "1_1") (pintype "passive"))
      (node (ref "R33") (pin "1") (pinfunction "1_1") (pintype "passive"))
      (node (ref "U5") (pin "3") (pinfunction "VOUT_3") (pintype "passive"))
    )
    (net (code "96") (name "2V5") (class "Default")
      (node (ref "C13") (pin "1") (pinfunction "1_1") (pintype "passive"))
      (node (ref "C15") (pin "1") (pinfunction "1_1") (pintype "passive"))
      (node (ref "C18") (pin "1") (pinfunction "1_1") (pintype "passive"))
      (node (ref "C21") (pin "1") (pinfunction "1_1") (pintype "passive"))
      (node (ref "C25") (pin "1") (pinfunction "1_1") (pintype "passive"))
      (node (ref "C27") (pin "1") (pinfunction "1_1") (pintype "passive"))
      (node (ref "C29") (pin "1") (pinfunction "1_1") (pintype "passive"))
      (node (ref "C31") (pin "1") (pinfunction "1_1") (pintype "passive"))
      (node (ref "C4") (pin "1") (pinfunction "1_1") (pintype "passive"))
      (node (ref "R16") (pin "1") (pinfunction "1_1") (pintype "passive"))
      (node (ref "R32") (pin "1") (pinfunction "1_1") (pintype "passive"))
      (node (ref "U4") (pin "3") (pinfunction "VOUT_3") (pintype "passive"))
    )
    (net (code "97") (name "3V3") (class "Default")
      (node (ref "C17") (pin "1") (pinfunction "1_1") (pintype "passive"))
      (node (ref "C2") (pin "1") (pinfunction "1_1") (pintype "passive"))
      (node (ref "C20") (pin "1") (pinfunction "1_1") (pintype "passive"))
      (node (ref "C24") (pin "1") (pinfunction "1_1") (pintype "passive"))
      (node (ref "C26") (pin "1") (pinfunction "1_1") (pintype "passive"))
      (node (ref "C28") (pin "1") (pinfunction "1_1") (pintype "passive"))
      (node (ref "C32") (pin "1") (pinfunction "1_1") (pintype "passive"))
      (node (ref "C35") (pin "1") (pinfunction "1_1") (pintype "passive"))
      (node (ref "C36") (pin "1") (pinfunction "1_1") (pintype "passive"))
      (node (ref "C37") (pin "1") (pinfunction "1_1") (pintype "passive"))
      (node (ref "C38") (pin "1") (pinfunction "1_1") (pintype "passive"))
      (node (ref "C39") (pin "1") (pinfunction "1_1") (pintype "passive"))
      (node (ref "C41") (pin "1") (pinfunction "1_1") (pintype "passive"))
      (node (ref "C6") (pin "1") (pinfunction "1_1") (pintype "passive"))
      (node (ref "C7") (pin "1") (pinfunction "1_1") (pintype "passive"))
      (node (ref "C8") (pin "1") (pinfunction "1_1") (pintype "passive"))
      (node (ref "DC14") (pin "A") (pinfunction "A_A") (pintype "passive"))
      (node (ref "JP2") (pin "2") (pinfunction "2_2") (pintype "passive"))
      (node (ref "P3") (pin "1") (pinfunction "1_1") (pintype "passive"))
      (node (ref "P3") (pin "17") (pinfunction "17_17") (pintype "passive"))
      (node (ref "R1") (pin "2") (pinfunction "2_2") (pintype "passive"))
      (node (ref "R15") (pin "1") (pinfunction "1_1") (pintype "passive"))
      (node (ref "R19") (pin "2") (pinfunction "2_2") (pintype "passive"))
      (node (ref "R20") (pin "2") (pinfunction "2_2") (pintype "passive"))
      (node (ref "R21") (pin "2") (pinfunction "2_2") (pintype "passive"))
      (node (ref "R22") (pin "1") (pinfunction "1_1") (pintype "passive"))
      (node (ref "R23") (pin "1") (pinfunction "1_1") (pintype "passive"))
      (node (ref "R35") (pin "1") (pinfunction "1_1") (pintype "passive"))
      (node (ref "R36") (pin "1") (pinfunction "1_1") (pintype "passive"))
      (node (ref "R39") (pin "1") (pinfunction "1_1") (pintype "passive"))
      (node (ref "R4") (pin "2") (pinfunction "2_2") (pintype "passive"))
      (node (ref "R5") (pin "2") (pinfunction "2_2") (pintype "passive"))
      (node (ref "R6") (pin "2") (pinfunction "2_2") (pintype "passive"))
      (node (ref "R8") (pin "2") (pinfunction "2_2") (pintype "passive"))
      (node (ref "U2") (pin "1") (pinfunction "VDD_1") (pintype "passive"))
      (node (ref "U3") (pin "3") (pinfunction "VOUT_3") (pintype "passive"))
      (node (ref "U4") (pin "1") (pinfunction "VIN_1") (pintype "passive"))
      (node (ref "U5") (pin "1") (pinfunction "VIN_1") (pintype "passive"))
    )
    (net (code "98") (name "3V3_RP") (class "Default")
      (node (ref "JP2") (pin "1") (pinfunction "1_1") (pintype "passive"))
      (node (ref "P2") (pin "1") (pinfunction "1_1") (pintype "passive"))
      (node (ref "P2") (pin "17") (pinfunction "17_17") (pintype "passive"))
    )
    (net (code "99") (name "5V") (class "Default")
      (node (ref "C5") (pin "1") (pinfunction "1_1") (pintype "passive"))
      (node (ref "D2") (pin "2") (pinfunction "K_2") (pintype "passive"))
      (node (ref "D4") (pin "2") (pinfunction "K_2") (pintype "passive"))
      (node (ref "D5") (pin "2") (pinfunction "K_2") (pintype "passive"))
      (node (ref "JP1") (pin "2") (pinfunction "2_2") (pintype "passive"))
      (node (ref "P3") (pin "2") (pinfunction "2_2") (pintype "passive"))
      (node (ref "P3") (pin "4") (pinfunction "4_4") (pintype "passive"))
      (node (ref "U3") (pin "1") (pinfunction "VIN_1") (pintype "passive"))
    )
    (net (code "100") (name "5V_RP") (class "Default")
      (node (ref "D2") (pin "1") (pinfunction "A_1") (pintype "passive"))
      (node (ref "JP1") (pin "1") (pinfunction "1_1") (pintype "passive"))
      (node (ref "P2") (pin "2") (pinfunction "2_2") (pintype "passive"))
      (node (ref "P2") (pin "4") (pinfunction "4_4") (pintype "passive"))
    )
    (net (code "101") (name "DGND") (class "Default")
      (node (ref "C1") (pin "1") (pinfunction "1_1") (pintype "passive"))
      (node (ref "C10") (pin "2") (pinfunction "2_2") (pintype "passive"))
      (node (ref "C11") (pin "2") (pinfunction "2_2") (pintype "passive"))
      (node (ref "C12") (pin "2") (pinfunction "2_2") (pintype "passive"))
      (node (ref "C13") (pin "2") (pinfunction "2_2") (pintype "passive"))
      (node (ref "C14") (pin "2") (pinfunction "2_2") (pintype "passive"))
      (node (ref "C15") (pin "2") (pinfunction "2_2") (pintype "passive"))
      (node (ref "C17") (pin "2") (pinfunction "2_2") (pintype "passive"))
      (node (ref "C18") (pin "2") (pinfunction "2_2") (pintype "passive"))
      (node (ref "C2") (pin "2") (pinfunction "2_2") (pintype "passive"))
      (node (ref "C20") (pin "2") (pinfunction "2_2") (pintype "passive"))
      (node (ref "C21") (pin "2") (pinfunction "2_2") (pintype "passive"))
      (node (ref "C24") (pin "2") (pinfunction "2_2") (pintype "passive"))
      (node (ref "C25") (pin "2") (pinfunction "2_2") (pintype "passive"))
      (node (ref "C26") (pin "2") (pinfunction "2_2") (pintype "passive"))
      (node (ref "C27") (pin "2") (pinfunction "2_2") (pintype "passive"))
      (node (ref "C28") (pin "2") (pinfunction "2_2") (pintype "passive"))
      (node (ref "C29") (pin "2") (pinfunction "2_2") (pintype "passive"))
      (node (ref "C3") (pin "2") (pinfunction "2_2") (pintype "passive"))
      (node (ref "C30") (pin "2") (pinfunction "2_2") (pintype "passive"))
      (node (ref "C31") (pin "2") (pinfunction "2_2") (pintype "passive"))
      (node (ref "C32") (pin "2") (pinfunction "2_2") (pintype "passive"))
      (node (ref "C33") (pin "2") (pinfunction "2_2") (pintype "passive"))
      (node (ref "C34") (pin "2") (pinfunction "2_2") (pintype "passive"))
      (node (ref "C35") (pin "2") (pinfunction "2_2") (pintype "passive"))
      (node (ref "C36") (pin "2") (pinfunction "2_2") (pintype "passive"))
      (node (ref "C37") (pin "2") (pinfunction "2_2") (pintype "passive"))
      (node (ref "C38") (pin "2") (pinfunction "2_2") (pintype "passive"))
      (node (ref "C39") (pin "2") (pinfunction "2_2") (pintype "passive"))
      (node (ref "C4") (pin "2") (pinfunction "2_2") (pintype "passive"))
      (node (ref "C40") (pin "2") (pinfunction "2_2") (pintype "passive"))
      (node (ref "C41") (pin "2") (pinfunction "2_2") (pintype "passive"))
      (node (ref "C5") (pin "2") (pinfunction "2_2") (pintype "passive"))
      (node (ref "C6") (pin "2") (pinfunction "2_2") (pintype "passive"))
      (node (ref "C7") (pin "2") (pinfunction "2_2") (pintype "passive"))
      (node (ref "C8") (pin "2") (pinfunction "2_2") (pintype "passive"))
      (node (ref "C9") (pin "2") (pinfunction "2_2") (pintype "passive"))
      (node (ref "D1") (pin "1") (pinfunction "GND_1") (pintype "passive"))
      (node (ref "DC1") (pin "C") (pinfunction "C_C") (pintype "passive"))
      (node (ref "DC10") (pin "C") (pinfunction "C_C") (pintype "passive"))
      (node (ref "DC11") (pin "C") (pinfunction "C_C") (pintype "passive"))
      (node (ref "DC12") (pin "C") (pinfunction "C_C") (pintype "passive"))
      (node (ref "DC13") (pin "C") (pinfunction "C_C") (pintype "passive"))
      (node (ref "DC2") (pin "C") (pinfunction "C_C") (pintype "passive"))
      (node (ref "DC6") (pin "C") (pinfunction "C_C") (pintype "passive"))
      (node (ref "DC7") (pin "C") (pinfunction "C_C") (pintype "passive"))
      (node (ref "DC8") (pin "C") (pinfunction "C_C") (pintype "passive"))
      (node (ref "DC9") (pin "C") (pinfunction "C_C") (pintype "passive"))
      (node (ref "P1") (pin "1") (pinfunction "GND_1") (pintype "power_in"))
      (node (ref "P1") (pin "G1") (pinfunction "GND_G1") (pintype "power_in"))
      (node (ref "P1") (pin "G2") (pinfunction "GND_G2") (pintype "power_in"))
      (node (ref "P1") (pin "G3") (pinfunction "GND_G3") (pintype "power_in"))
      (node (ref "P1") (pin "G4") (pinfunction "GND_G4") (pintype "power_in"))
      (node (ref "P2") (pin "14") (pinfunction "14_14") (pintype "passive"))
      (node (ref "P2") (pin "20") (pinfunction "20_20") (pintype "passive"))
      (node (ref "P2") (pin "25") (pinfunction "25_25") (pintype "passive"))
      (node (ref "P2") (pin "30") (pinfunction "30_30") (pintype "passive"))
      (node (ref "P2") (pin "34") (pinfunction "34_34") (pintype "passive"))
      (node (ref "P2") (pin "39") (pinfunction "39_39") (pintype "passive"))
      (node (ref "P2") (pin "6") (pinfunction "6_6") (pintype "passive"))
      (node (ref "P2") (pin "9") (pinfunction "9_9") (pintype "passive"))
      (node (ref "P3") (pin "14") (pinfunction "14_14") (pintype "passive"))
      (node (ref "P3") (pin "20") (pinfunction "20_20") (pintype "passive"))
      (node (ref "P3") (pin "25") (pinfunction "25_25") (pintype "passive"))
      (node (ref "P3") (pin "30") (pinfunction "30_30") (pintype "passive"))
      (node (ref "P3") (pin "34") (pinfunction "34_34") (pintype "passive"))
      (node (ref "P3") (pin "39") (pinfunction "39_39") (pintype "passive"))
      (node (ref "P3") (pin "6") (pinfunction "6_6") (pintype "passive"))
      (node (ref "P3") (pin "9") (pinfunction "9_9") (pintype "passive"))
      (node (ref "P4") (pin "2") (pinfunction "2_2") (pintype "passive"))
      (node (ref "P6") (pin "1") (pinfunction "1_1") (pintype "passive"))
      (node (ref "R17") (pin "1") (pinfunction "1_1") (pintype "passive"))
      (node (ref "R32") (pin "2") (pinfunction "2_2") (pintype "passive"))
      (node (ref "R33") (pin "2") (pinfunction "2_2") (pintype "passive"))
      (node (ref "R37") (pin "1") (pinfunction "1_1") (pintype "passive"))
      (node (ref "R9") (pin "2") (pinfunction "2_2") (pintype "passive"))
      (node (ref "SW1") (pin "1") (pinfunction "1_1") (pintype "passive"))
      (node (ref "SW2") (pin "1") (pinfunction "1_1") (pintype "passive"))
      (node (ref "SW2") (pin "3") (pinfunction "3_3") (pintype "passive"))
      (node (ref "SW2") (pin "5") (pinfunction "5_5") (pintype "passive"))
      (node (ref "SW2") (pin "7") (pinfunction "7_7") (pintype "passive"))
      (node (ref "U2") (pin "13") (pinfunction "GND_13") (pintype "passive"))
      (node (ref "U2") (pin "18") (pinfunction "GND_18") (pintype "passive"))
      (node (ref "U2") (pin "9") (pinfunction "GND_9") (pintype "passive"))
      (node (ref "U3") (pin "2") (pinfunction "GND_2") (pintype "passive"))
      (node (ref "U3") (pin "4") (pinfunction "GND_4") (pintype "passive"))
      (node (ref "U4") (pin "2") (pinfunction "GND_2") (pintype "passive"))
      (node (ref "U4") (pin "4") (pinfunction "GND_4") (pintype "passive"))
      (node (ref "U5") (pin "2") (pinfunction "GND_2") (pintype "passive"))
      (node (ref "U5") (pin "4") (pinfunction "GND_4") (pintype "passive"))
      (node (ref "U6") (pin "2") (pinfunction "GND_2") (pintype "passive"))
    )
    (net (code "102") (name "Net-(D5-A)") (class "Default")
      (node (ref "D5") (pin "1") (pinfunction "A_1") (pintype "passive"))
      (node (ref "P4") (pin "1") (pinfunction "1_1") (pintype "passive"))
    )
    (net (code "103") (name "Net-(DC1-PadA)") (class "Default")
      (node (ref "DC1") (pin "A") (pinfunction "A_A") (pintype "passive"))
      (node (ref "R24") (pin "1") (pinfunction "1_1") (pintype "passive"))
    )
    (net (code "104") (name "Net-(DC2-PadA)") (class "Default")
      (node (ref "DC2") (pin "A") (pinfunction "A_A") (pintype "passive"))
      (node (ref "R7") (pin "2") (pinfunction "2_2") (pintype "passive"))
    )
    (net (code "105") (name "Net-(DC3-PadA)") (class "Default")
      (node (ref "DC3") (pin "A") (pinfunction "A_A") (pintype "passive"))
      (node (ref "R11") (pin "1") (pinfunction "1_1") (pintype "passive"))
    )
    (net (code "106") (name "Net-(DC4-PadC)") (class "Default")
      (node (ref "DC4") (pin "C") (pinfunction "C_C") (pintype "passive"))
      (node (ref "R17") (pin "2") (pinfunction "2_2") (pintype "passive"))
    )
    (net (code "107") (name "Net-(DC5-PadA)") (class "Default")
      (node (ref "DC5") (pin "A") (pinfunction "A_A") (pintype "passive"))
      (node (ref "R13") (pin "1") (pinfunction "1_1") (pintype "passive"))
    )
    (net (code "108") (name "Net-(DC7-PadA)") (class "Default")
      (node (ref "DC7") (pin "A") (pinfunction "A_A") (pintype "passive"))
      (node (ref "R25") (pin "1") (pinfunction "1_1") (pintype "passive"))
    )
    (net (code "109") (name "Net-(DC8-PadA)") (class "Default")
      (node (ref "DC8") (pin "A") (pinfunction "A_A") (pintype "passive"))
      (node (ref "R26") (pin "1") (pinfunction "1_1") (pintype "passive"))
    )
    (net (code "110") (name "Net-(DC9-PadA)") (class "Default")
      (node (ref "DC9") (pin "A") (pinfunction "A_A") (pintype "passive"))
      (node (ref "R27") (pin "1") (pinfunction "1_1") (pintype "passive"))
    )
    (net (code "111") (name "Net-(DC10-PadA)") (class "Default")
      (node (ref "DC10") (pin "A") (pinfunction "A_A") (pintype "passive"))
      (node (ref "R28") (pin "1") (pinfunction "1_1") (pintype "passive"))
    )
    (net (code "112") (name "Net-(DC11-PadA)") (class "Default")
      (node (ref "DC11") (pin "A") (pinfunction "A_A") (pintype "passive"))
      (node (ref "R29") (pin "1") (pinfunction "1_1") (pintype "passive"))
    )
    (net (code "113") (name "Net-(DC12-PadA)") (class "Default")
      (node (ref "DC12") (pin "A") (pinfunction "A_A") (pintype "passive"))
      (node (ref "R30") (pin "1") (pinfunction "1_1") (pintype "passive"))
    )
    (net (code "114") (name "Net-(DC13-PadA)") (class "Default")
      (node (ref "DC13") (pin "A") (pinfunction "A_A") (pintype "passive"))
      (node (ref "R31") (pin "1") (pinfunction "1_1") (pintype "passive"))
    )
    (net (code "115") (name "Net-(DC14-PadC)") (class "Default")
      (node (ref "DC14") (pin "C") (pinfunction "C_C") (pintype "passive"))
      (node (ref "R37") (pin "2") (pinfunction "2_2") (pintype "passive"))
    )
    (net (code "116") (name "Net-(DC15-PadA)") (class "Default")
      (node (ref "DC15") (pin "A") (pinfunction "A_A") (pintype "passive"))
      (node (ref "R39") (pin "2") (pinfunction "2_2") (pintype "passive"))
    )
    (net (code "117") (name "Net-(Q1-B)") (class "Default")
      (node (ref "Q1") (pin "1") (pinfunction "B_1") (pintype "passive"))
      (node (ref "R12") (pin "1") (pinfunction "1_1") (pintype "passive"))
    )
    (net (code "118") (name "Net-(Q2-B)") (class "Default")
      (node (ref "Q2") (pin "1") (pinfunction "B_1") (pintype "passive"))
      (node (ref "R18") (pin "1") (pinfunction "1_1") (pintype "passive"))
    )
    (net (code "119") (name "Net-(R34-Pad1)") (class "Default")
      (node (ref "R34") (pin "1") (pinfunction "1_1") (pintype "passive"))
      (node (ref "SW1") (pin "2") (pinfunction "2_2") (pintype "passive"))
    )
    (net (code "120") (name "VDDUSB") (class "Default")
      (node (ref "C12") (pin "1") (pinfunction "1_1") (pintype "passive"))
      (node (ref "C14") (pin "1") (pinfunction "1_1") (pintype "passive"))
      (node (ref "D1") (pin "4") (pinfunction "4_4") (pintype "passive"))
      (node (ref "D4") (pin "1") (pinfunction "A_1") (pintype "passive"))
      (node (ref "P1") (pin "5") (pinfunction "VBUS_5") (pintype "power_in"))
      (node (ref "U6") (pin "7") (pinfunction "REGIN_7") (pintype "passive"))
      (node (ref "U6") (pin "8") (pinfunction "VBUS_8") (pintype "passive"))
    )
    (net (code "121") (name "VIO") (class "Default")
      (node (ref "C3") (pin "1") (pinfunction "1_1") (pintype "passive"))
      (node (ref "C9") (pin "1") (pinfunction "1_1") (pintype "passive"))
      (node (ref "DC4") (pin "A") (pinfunction "A_A") (pintype "passive"))
      (node (ref "R10") (pin "2") (pinfunction "2_2") (pintype "passive"))
      (node (ref "R11") (pin "2") (pinfunction "2_2") (pintype "passive"))
      (node (ref "R13") (pin "2") (pinfunction "2_2") (pintype "passive"))
      (node (ref "U6") (pin "5") (pinfunction "VIO_5") (pintype "passive"))
      (node (ref "U6") (pin "6") (pinfunction "VDD_6") (pintype "passive"))
    )
    (net (code "122") (name "unconnected-(P1-ID-Pad2)") (class "Default")
      (node (ref "P1") (pin "2") (pinfunction "ID_2") (pintype "input+no_connect"))
    )
    (net (code "123") (name "unconnected-(U6-CTS-Pad18)") (class "Default")
      (node (ref "U6") (pin "18") (pinfunction "CTS_18") (pintype "passive+no_connect"))
    )
    (net (code "124") (name "unconnected-(U6-DCD-Pad24)") (class "Default")
      (node (ref "U6") (pin "24") (pinfunction "DCD_24") (pintype "passive+no_connect"))
    )
    (net (code "125") (name "unconnected-(U6-DSR-Pad22)") (class "Default")
      (node (ref "U6") (pin "22") (pinfunction "DSR_22") (pintype "passive+no_connect"))
    )
    (net (code "126") (name "unconnected-(U6-GPIO.2-Pad12)") (class "Default")
      (node (ref "U6") (pin "12") (pinfunction "GPIO.2_12") (pintype "passive+no_connect"))
    )
    (net (code "127") (name "unconnected-(U6-GPIO.3-Pad11)") (class "Default")
      (node (ref "U6") (pin "11") (pinfunction "GPIO.3_11") (pintype "passive+no_connect"))
    )
    (net (code "128") (name "unconnected-(U6-NC-Pad10)") (class "Default")
      (node (ref "U6") (pin "10") (pinfunction "NC_10") (pintype "passive+no_connect"))
    )
    (net (code "129") (name "unconnected-(U6-RI-Pad1)") (class "Default")
      (node (ref "U6") (pin "1") (pinfunction "RI_1") (pintype "passive+no_connect"))
    )
    (net (code "130") (name "unconnected-(U6-SUSPEND-Pad15)") (class "Default")
      (node (ref "U6") (pin "15") (pinfunction "SUSPEND_15") (pintype "passive+no_connect"))
    )
    (net (code "131") (name "unconnected-(U6-SUSPEND-Pad17)") (class "Default")
      (node (ref "U6") (pin "17") (pinfunction "SUSPEND_17") (pintype "passive+no_connect"))
    )
    (net (code "132") (name "unconnected-(U6-~{RST}-Pad9)") (class "Default")
      (node (ref "U6") (pin "9") (pinfunction "~{RST}_9") (pintype "passive+no_connect"))
    )
  )
)
